# pager_v2.net
KiCad netlist of a schematic drawn in EAGLE
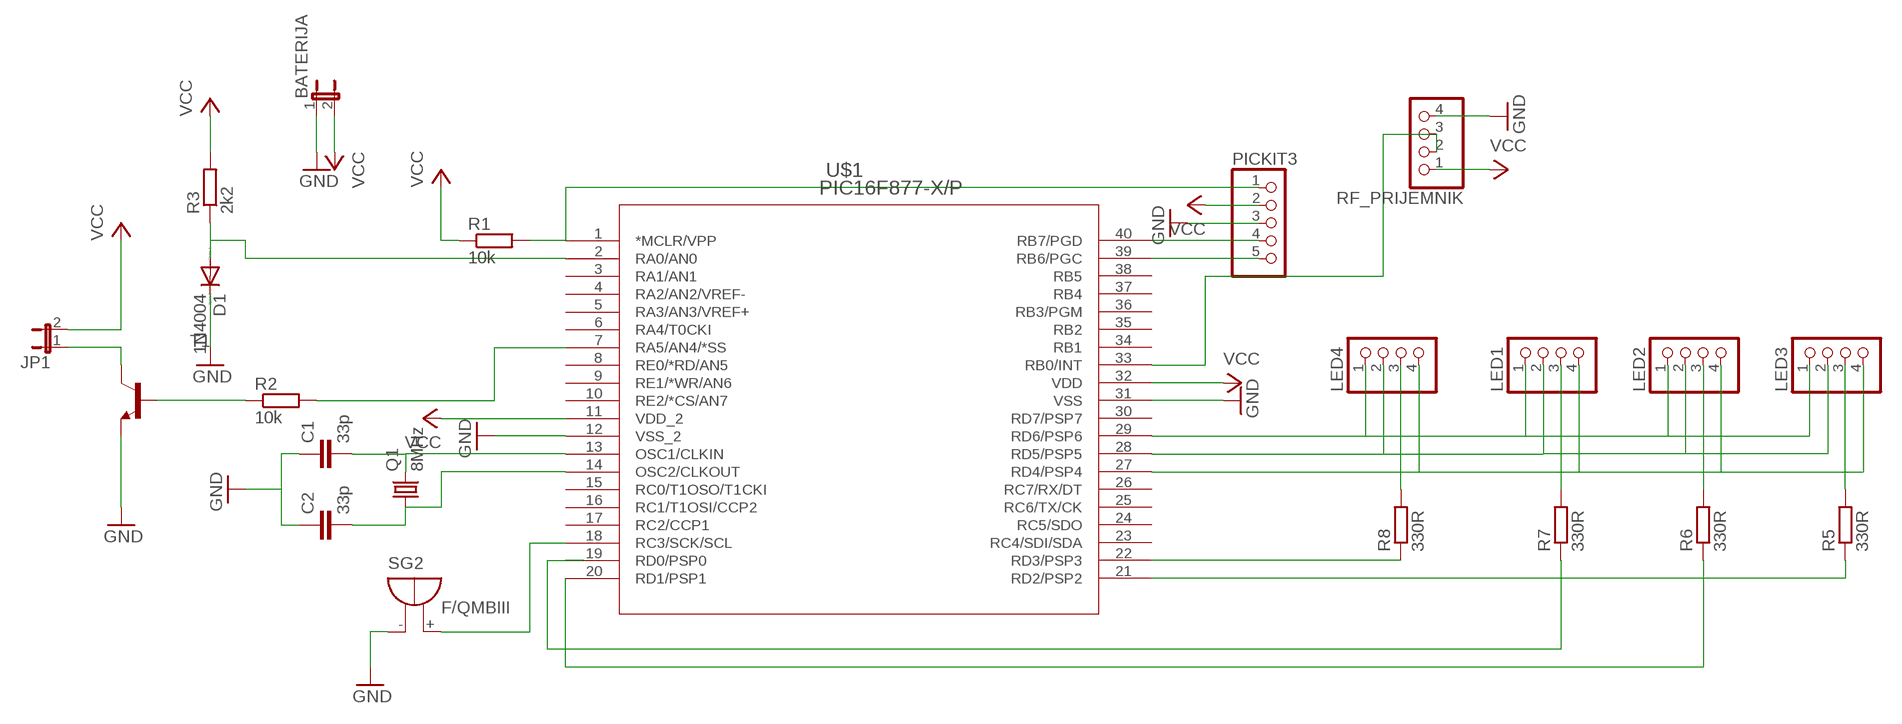
[diagram p0: schematic, sheet 1]

(export (version "E")
  (design (tool "Eeschema 10.0.6"))
  (components
    (comp (ref "BATERIJA")
      (value "JP1E")
      (footprint "eagle-import:JP1")
      (libsource (lib "eagle-import") (part "JP1E"))
    )
    (comp (ref "C1")
      (value "33p")
      (footprint "eagle-import:C025-024X044")
      (libsource (lib "eagle-import") (part "C-EU025-024X044"))
    )
    (comp (ref "C2")
      (value "33p")
      (footprint "eagle-import:C025-024X044")
      (libsource (lib "eagle-import") (part "C-EU025-024X044"))
    )
    (comp (ref "D1")
      (value "1N4004")
      (footprint "eagle-import:DO41-10")
      (libsource (lib "eagle-import") (part "1N4004"))
    )
    (comp (ref "JP1")
      (value "JP1E")
      (footprint "eagle-import:JP1")
      (libsource (lib "eagle-import") (part "JP1E"))
    )
    (comp (ref "LED1")
      (value "PINHD-1X4")
      (footprint "eagle-import:1X04")
      (libsource (lib "eagle-import") (part "PINHD-1X4"))
    )
    (comp (ref "LED2")
      (value "PINHD-1X4")
      (footprint "eagle-import:1X04")
      (libsource (lib "eagle-import") (part "PINHD-1X4"))
    )
    (comp (ref "LED3")
      (value "PINHD-1X4")
      (footprint "eagle-import:1X04")
      (libsource (lib "eagle-import") (part "PINHD-1X4"))
    )
    (comp (ref "LED4")
      (value "PINHD-1X4")
      (footprint "eagle-import:1X04")
      (libsource (lib "eagle-import") (part "PINHD-1X4"))
    )
    (comp (ref "PICKIT3")
      (value "PINHD-1X5")
      (footprint "eagle-import:1X05")
      (libsource (lib "eagle-import") (part "PINHD-1X5"))
    )
    (comp (ref "Q1")
      (value "8MHz")
      (footprint "eagle-import:HC49_S")
      (libsource (lib "eagle-import") (part "CRYSTALHC49S"))
    )
    (comp (ref "R1")
      (value "10k")
      (footprint "eagle-import:0207_10")
      (libsource (lib "eagle-import") (part "R-EU_0207/10"))
    )
    (comp (ref "R2")
      (value "10k")
      (footprint "eagle-import:0207_10")
      (libsource (lib "eagle-import") (part "R-EU_0207/10"))
    )
    (comp (ref "R3")
      (value "2k2")
      (footprint "eagle-import:0207_10")
      (libsource (lib "eagle-import") (part "R-EU_0207/10"))
    )
    (comp (ref "R5")
      (value "330R")
      (footprint "eagle-import:0207_10")
      (libsource (lib "eagle-import") (part "R-EU_0207/10"))
    )
    (comp (ref "R6")
      (value "330R")
      (footprint "eagle-import:0207_10")
      (libsource (lib "eagle-import") (part "R-EU_0207/10"))
    )
    (comp (ref "R7")
      (value "330R")
      (footprint "eagle-import:0207_10")
      (libsource (lib "eagle-import") (part "R-EU_0207/10"))
    )
    (comp (ref "R8")
      (value "330R")
      (footprint "eagle-import:0207_10")
      (libsource (lib "eagle-import") (part "R-EU_0207/10"))
    )
    (comp (ref "RF_PRIJEMNIK")
      (value "PINHD-1X4")
      (footprint "eagle-import:1X04")
      (libsource (lib "eagle-import") (part "PINHD-1X4"))
    )
    (comp (ref "SG2")
      (value "F/QMBIII")
      (footprint "eagle-import:F_QMBIII")
      (libsource (lib "eagle-import") (part "F/QMBIII"))
    )
    (comp (ref "T1")
      (value "-NPN-TO92-EBC")
      (footprint "eagle-import:TO92-EBC")
      (libsource (lib "eagle-import") (part "-NPN-TO92-EBC"))
    )
    (comp (ref "U$1")
      (value "PIC16F877-X/P")
      (footprint "eagle-import:PDIP40_600MC")
      (libsource (lib "eagle-import") (part "PIC16F877-X/P"))
    )
  )
  (nets
    (net (code "1") (name "GND") (class "Default")
      (node (ref "BATERIJA") (pin "1") (pinfunction "1_1") (pintype "passive"))
      (node (ref "C1") (pin "1") (pinfunction "1_1") (pintype "passive"))
      (node (ref "C2") (pin "1") (pinfunction "1_1") (pintype "passive"))
      (node (ref "D1") (pin "C") (pinfunction "C_C") (pintype "passive"))
      (node (ref "PICKIT3") (pin "3") (pinfunction "3_3") (pintype "passive"))
      (node (ref "RF_PRIJEMNIK") (pin "4") (pinfunction "4_4") (pintype "passive"))
      (node (ref "SG2") (pin "-") (pinfunction "+_-") (pintype "passive"))
      (node (ref "T1") (pin "E") (pinfunction "E_E") (pintype "passive"))
      (node (ref "U$1") (pin "12") (pinfunction "VSS_2_12") (pintype "passive"))
      (node (ref "U$1") (pin "31") (pinfunction "VSS_31") (pintype "passive"))
    )
    (net (code "2") (name "Net-(JP1-Pad1)") (class "Default")
      (node (ref "JP1") (pin "1") (pinfunction "1_1") (pintype "passive"))
      (node (ref "T1") (pin "C") (pinfunction "C_C") (pintype "passive"))
    )
    (net (code "3") (name "Net-(LED1-Pad3)") (class "Default")
      (node (ref "LED1") (pin "3") (pinfunction "3_3") (pintype "passive"))
      (node (ref "R7") (pin "2") (pinfunction "2_2") (pintype "passive"))
    )
    (net (code "4") (name "Net-(LED2-Pad3)") (class "Default")
      (node (ref "LED2") (pin "3") (pinfunction "3_3") (pintype "passive"))
      (node (ref "R6") (pin "2") (pinfunction "2_2") (pintype "passive"))
    )
    (net (code "5") (name "Net-(LED3-Pad3)") (class "Default")
      (node (ref "LED3") (pin "3") (pinfunction "3_3") (pintype "passive"))
      (node (ref "R5") (pin "2") (pinfunction "2_2") (pintype "passive"))
    )
    (net (code "6") (name "Net-(LED4-Pad3)") (class "Default")
      (node (ref "LED4") (pin "3") (pinfunction "3_3") (pintype "passive"))
      (node (ref "R8") (pin "2") (pinfunction "2_2") (pintype "passive"))
    )
    (net (code "7") (name "Net-(R2-Pad1)") (class "Default")
      (node (ref "R2") (pin "1") (pinfunction "1_1") (pintype "passive"))
      (node (ref "T1") (pin "B") (pinfunction "B_B") (pintype "passive"))
    )
    (net (code "8") (name "Net-(SG2--)") (class "Default")
      (node (ref "SG2") (pin "+") (pinfunction "-_+") (pintype "passive"))
      (node (ref "U$1") (pin "18") (pinfunction "RC3/SCK/SCL_18") (pintype "passive"))
    )
    (net (code "9") (name "Net-(U$1-*MCLR{slash}VPP)") (class "Default")
      (node (ref "PICKIT3") (pin "1") (pinfunction "1_1") (pintype "passive"))
      (node (ref "R1") (pin "2") (pinfunction "2_2") (pintype "passive"))
      (node (ref "U$1") (pin "1") (pinfunction "*MCLR/VPP_1") (pintype "passive"))
    )
    (net (code "10") (name "Net-(U$1-OSC1{slash}CLKIN)") (class "Default")
      (node (ref "C1") (pin "2") (pinfunction "2_2") (pintype "passive"))
      (node (ref "Q1") (pin "2") (pinfunction "2_2") (pintype "passive"))
      (node (ref "U$1") (pin "13") (pinfunction "OSC1/CLKIN_13") (pintype "passive"))
    )
    (net (code "11") (name "Net-(U$1-OSC2{slash}CLKOUT)") (class "Default")
      (node (ref "C2") (pin "2") (pinfunction "2_2") (pintype "passive"))
      (node (ref "Q1") (pin "1") (pinfunction "1_1") (pintype "passive"))
      (node (ref "U$1") (pin "14") (pinfunction "OSC2/CLKOUT_14") (pintype "passive"))
    )
    (net (code "12") (name "Net-(U$1-RA0{slash}AN0)") (class "Default")
      (node (ref "D1") (pin "A") (pinfunction "A_A") (pintype "passive"))
      (node (ref "R3") (pin "1") (pinfunction "1_1") (pintype "passive"))
      (node (ref "U$1") (pin "2") (pinfunction "RA0/AN0_2") (pintype "passive"))
    )
    (net (code "13") (name "Net-(U$1-RA5{slash}AN4{slash}*SS)") (class "Default")
      (node (ref "R2") (pin "2") (pinfunction "2_2") (pintype "passive"))
      (node (ref "U$1") (pin "7") (pinfunction "RA5/AN4/*SS_7") (pintype "passive"))
    )
    (net (code "14") (name "Net-(U$1-RB0{slash}INT)") (class "Default")
      (node (ref "RF_PRIJEMNIK") (pin "2") (pinfunction "2_2") (pintype "passive"))
      (node (ref "RF_PRIJEMNIK") (pin "3") (pinfunction "3_3") (pintype "passive"))
      (node (ref "U$1") (pin "33") (pinfunction "RB0/INT_33") (pintype "passive"))
    )
    (net (code "15") (name "Net-(U$1-RB6{slash}PGC)") (class "Default")
      (node (ref "PICKIT3") (pin "5") (pinfunction "5_5") (pintype "passive"))
      (node (ref "U$1") (pin "39") (pinfunction "RB6/PGC_39") (pintype "passive"))
    )
    (net (code "16") (name "Net-(U$1-RB7{slash}PGD)") (class "Default")
      (node (ref "PICKIT3") (pin "4") (pinfunction "4_4") (pintype "passive"))
      (node (ref "U$1") (pin "40") (pinfunction "RB7/PGD_40") (pintype "passive"))
    )
    (net (code "17") (name "Net-(U$1-RD0{slash}PSP0)") (class "Default")
      (node (ref "R7") (pin "1") (pinfunction "1_1") (pintype "passive"))
      (node (ref "U$1") (pin "19") (pinfunction "RD0/PSP0_19") (pintype "passive"))
    )
    (net (code "18") (name "Net-(U$1-RD1{slash}PSP1)") (class "Default")
      (node (ref "R6") (pin "1") (pinfunction "1_1") (pintype "passive"))
      (node (ref "U$1") (pin "20") (pinfunction "RD1/PSP1_20") (pintype "passive"))
    )
    (net (code "19") (name "Net-(U$1-RD2{slash}PSP2)") (class "Default")
      (node (ref "R5") (pin "1") (pinfunction "1_1") (pintype "passive"))
      (node (ref "U$1") (pin "21") (pinfunction "RD2/PSP2_21") (pintype "passive"))
    )
    (net (code "20") (name "Net-(U$1-RD3{slash}PSP3)") (class "Default")
      (node (ref "R8") (pin "1") (pinfunction "1_1") (pintype "passive"))
      (node (ref "U$1") (pin "22") (pinfunction "RD3/PSP3_22") (pintype "passive"))
    )
    (net (code "21") (name "Net-(U$1-RD4{slash}PSP4)") (class "Default")
      (node (ref "LED1") (pin "4") (pinfunction "4_4") (pintype "passive"))
      (node (ref "LED2") (pin "4") (pinfunction "4_4") (pintype "passive"))
      (node (ref "LED3") (pin "4") (pinfunction "4_4") (pintype "passive"))
      (node (ref "LED4") (pin "4") (pinfunction "4_4") (pintype "passive"))
      (node (ref "U$1") (pin "27") (pinfunction "RD4/PSP4_27") (pintype "passive"))
    )
    (net (code "22") (name "Net-(U$1-RD5{slash}PSP5)") (class "Default")
      (node (ref "LED1") (pin "2") (pinfunction "2_2") (pintype "passive"))
      (node (ref "LED2") (pin "2") (pinfunction "2_2") (pintype "passive"))
      (node (ref "LED3") (pin "2") (pinfunction "2_2") (pintype "passive"))
      (node (ref "LED4") (pin "2") (pinfunction "2_2") (pintype "passive"))
      (node (ref "U$1") (pin "28") (pinfunction "RD5/PSP5_28") (pintype "passive"))
    )
    (net (code "23") (name "Net-(U$1-RD6{slash}PSP6)") (class "Default")
      (node (ref "LED1") (pin "1") (pinfunction "1_1") (pintype "passive"))
      (node (ref "LED2") (pin "1") (pinfunction "1_1") (pintype "passive"))
      (node (ref "LED3") (pin "1") (pinfunction "1_1") (pintype "passive"))
      (node (ref "LED4") (pin "1") (pinfunction "1_1") (pintype "passive"))
      (node (ref "U$1") (pin "29") (pinfunction "RD6/PSP6_29") (pintype "passive"))
    )
    (net (code "24") (name "VCC") (class "Default")
      (node (ref "BATERIJA") (pin "2") (pinfunction "2_2") (pintype "passive"))
      (node (ref "JP1") (pin "2") (pinfunction "2_2") (pintype "passive"))
      (node (ref "PICKIT3") (pin "2") (pinfunction "2_2") (pintype "passive"))
      (node (ref "R1") (pin "1") (pinfunction "1_1") (pintype "passive"))
      (node (ref "R3") (pin "2") (pinfunction "2_2") (pintype "passive"))
      (node (ref "RF_PRIJEMNIK") (pin "1") (pinfunction "1_1") (pintype "passive"))
      (node (ref "U$1") (pin "11") (pinfunction "VDD_2_11") (pintype "passive"))
      (node (ref "U$1") (pin "32") (pinfunction "VDD_32") (pintype "passive"))
    )
    (net (code "25") (name "unconnected-(U$1-RA1{slash}AN1-Pad3)") (class "Default")
      (node (ref "U$1") (pin "3") (pinfunction "RA1/AN1_3") (pintype "passive"))
    )
    (net (code "26") (name "unconnected-(U$1-RA2{slash}AN2{slash}VREF--Pad4)") (class "Default")
      (node (ref "U$1") (pin "4") (pinfunction "RA2/AN2/VREF-_4") (pintype "passive"))
    )
    (net (code "27") (name "unconnected-(U$1-RA3{slash}AN3{slash}VREF+-Pad5)") (class "Default")
      (node (ref "U$1") (pin "5") (pinfunction "RA3/AN3/VREF+_5") (pintype "passive"))
    )
    (net (code "28") (name "unconnected-(U$1-RA4{slash}T0CKI-Pad6)") (class "Default")
      (node (ref "U$1") (pin "6") (pinfunction "RA4/T0CKI_6") (pintype "passive"))
    )
    (net (code "29") (name "unconnected-(U$1-RB1-Pad34)") (class "Default")
      (node (ref "U$1") (pin "34") (pinfunction "RB1_34") (pintype "passive"))
    )
    (net (code "30") (name "unconnected-(U$1-RB2-Pad35)") (class "Default")
      (node (ref "U$1") (pin "35") (pinfunction "RB2_35") (pintype "passive"))
    )
    (net (code "31") (name "unconnected-(U$1-RB3{slash}PGM-Pad36)") (class "Default")
      (node (ref "U$1") (pin "36") (pinfunction "RB3/PGM_36") (pintype "passive"))
    )
    (net (code "32") (name "unconnected-(U$1-RB4-Pad37)") (class "Default")
      (node (ref "U$1") (pin "37") (pinfunction "RB4_37") (pintype "passive"))
    )
    (net (code "33") (name "unconnected-(U$1-RB5-Pad38)") (class "Default")
      (node (ref "U$1") (pin "38") (pinfunction "RB5_38") (pintype "passive"))
    )
    (net (code "34") (name "unconnected-(U$1-RC0{slash}T1OSO{slash}T1CKI-Pad15)") (class "Default")
      (node (ref "U$1") (pin "15") (pinfunction "RC0/T1OSO/T1CKI_15") (pintype "passive"))
    )
    (net (code "35") (name "unconnected-(U$1-RC1{slash}T1OSI{slash}CCP2-Pad16)") (class "Default")
      (node (ref "U$1") (pin "16") (pinfunction "RC1/T1OSI/CCP2_16") (pintype "passive"))
    )
    (net (code "36") (name "unconnected-(U$1-RC2{slash}CCP1-Pad17)") (class "Default")
      (node (ref "U$1") (pin "17") (pinfunction "RC2/CCP1_17") (pintype "passive"))
    )
    (net (code "37") (name "unconnected-(U$1-RC4{slash}SDI{slash}SDA-Pad23)") (class "Default")
      (node (ref "U$1") (pin "23") (pinfunction "RC4/SDI/SDA_23") (pintype "passive"))
    )
    (net (code "38") (name "unconnected-(U$1-RC5{slash}SDO-Pad24)") (class "Default")
      (node (ref "U$1") (pin "24") (pinfunction "RC5/SDO_24") (pintype "passive"))
    )
    (net (code "39") (name "unconnected-(U$1-RC6{slash}TX{slash}CK-Pad25)") (class "Default")
      (node (ref "U$1") (pin "25") (pinfunction "RC6/TX/CK_25") (pintype "passive"))
    )
    (net (code "40") (name "unconnected-(U$1-RC7{slash}RX{slash}DT-Pad26)") (class "Default")
      (node (ref "U$1") (pin "26") (pinfunction "RC7/RX/DT_26") (pintype "passive"))
    )
    (net (code "41") (name "unconnected-(U$1-RD7{slash}PSP7-Pad30)") (class "Default")
      (node (ref "U$1") (pin "30") (pinfunction "RD7/PSP7_30") (pintype "passive"))
    )
    (net (code "42") (name "unconnected-(U$1-RE0{slash}*RD{slash}AN5-Pad8)") (class "Default")
      (node (ref "U$1") (pin "8") (pinfunction "RE0/*RD/AN5_8") (pintype "passive"))
    )
    (net (code "43") (name "unconnected-(U$1-RE1{slash}*WR{slash}AN6-Pad9)") (class "Default")
      (node (ref "U$1") (pin "9") (pinfunction "RE1/*WR/AN6_9") (pintype "passive"))
    )
    (net (code "44") (name "unconnected-(U$1-RE2{slash}*CS{slash}AN7-Pad10)") (class "Default")
      (node (ref "U$1") (pin "10") (pinfunction "RE2/*CS/AN7_10") (pintype "passive"))
    )
  )
)
